# T01_Synth_Glove_v5.net
KiCad netlist of a schematic drawn in EAGLE
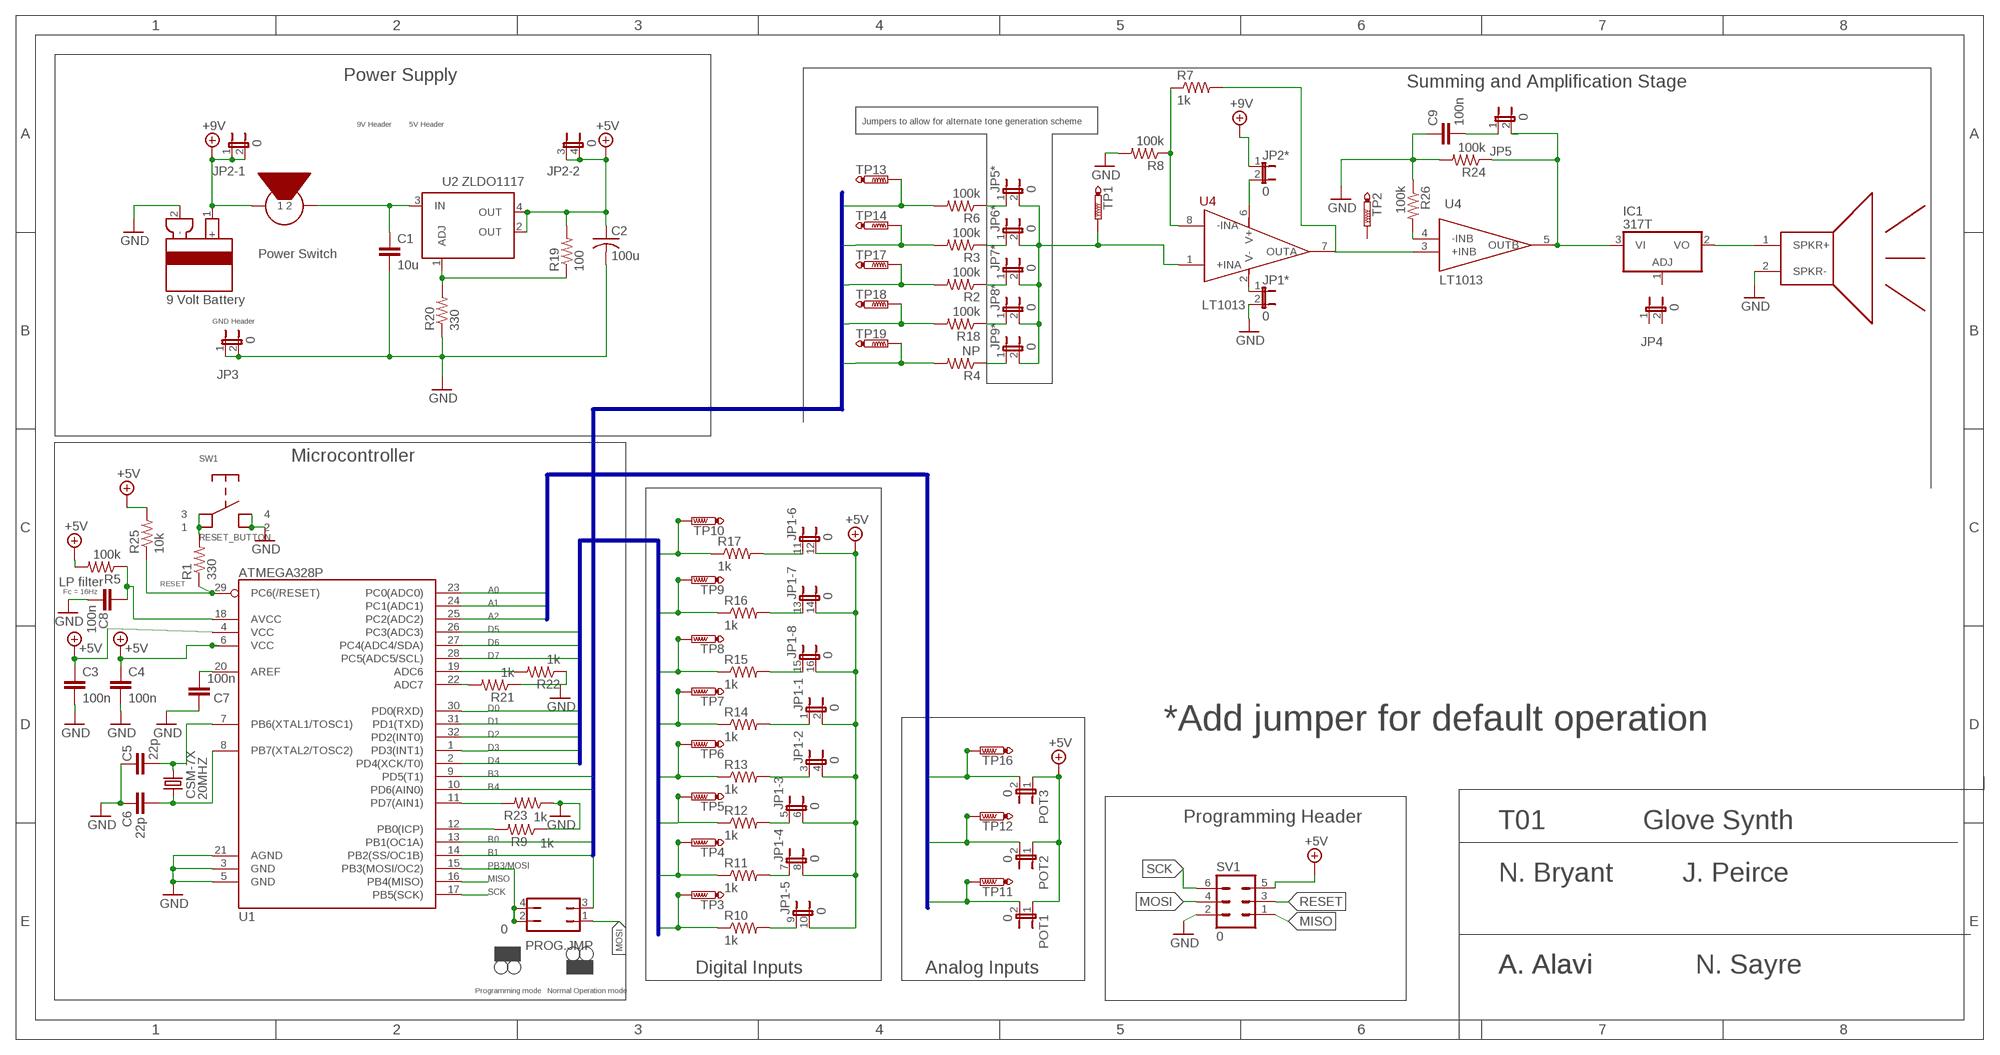
[diagram p0: schematic, sheet 1]

(export (version "E")
  (design (tool "Eeschema 10.0.6"))
  (components
    (comp (ref "20MHZ")
      (value "CSM-7X")
      (footprint "eagle-import:CSM-7X-DU")
      (libsource (lib "eagle-import") (part "CSM-7X-DU"))
    )
    (comp (ref "C1")
      (value "10u")
      (footprint "eagle-import:0603-CAP")
      (libsource (lib "eagle-import") (part "CAP0603-CAP"))
    )
    (comp (ref "C2")
      (value "100u")
      (footprint "eagle-import:C075-042X103")
      (libsource (lib "eagle-import") (part "C-US075-042X103"))
    )
    (comp (ref "C3")
      (value "100n")
      (footprint "eagle-import:0603-CAP")
      (libsource (lib "eagle-import") (part "CAP0603-CAP"))
    )
    (comp (ref "C4")
      (value "100n")
      (footprint "eagle-import:0603-CAP")
      (libsource (lib "eagle-import") (part "CAP0603-CAP"))
    )
    (comp (ref "C5")
      (value "22p")
      (footprint "eagle-import:0603-CAP")
      (libsource (lib "eagle-import") (part "CAP0603-CAP"))
    )
    (comp (ref "C6")
      (value "22p")
      (footprint "eagle-import:0603-CAP")
      (libsource (lib "eagle-import") (part "CAP0603-CAP"))
    )
    (comp (ref "C7")
      (value "100n")
      (footprint "eagle-import:0603-CAP")
      (libsource (lib "eagle-import") (part "CAP0603-CAP"))
    )
    (comp (ref "C8")
      (value "100n")
      (footprint "eagle-import:0603-CAP")
      (libsource (lib "eagle-import") (part "CAP0603-CAP"))
    )
    (comp (ref "C9")
      (value "100n")
      (footprint "eagle-import:0603-CAP")
      (libsource (lib "eagle-import") (part "CAP0603-CAP"))
    )
    (comp (ref "IC1")
      (value "317T")
      (footprint "eagle-import:TO220H")
      (libsource (lib "eagle-import") (part "317T"))
    )
    (comp (ref "JP1")
      (value "0")
      (footprint "eagle-import:JP8Q")
      (libsource (lib "eagle-import") (part "JP8QE"))
    )
    (comp (ref "JP1*")
      (value "0")
      (footprint "eagle-import:JP1")
      (libsource (lib "eagle-import") (part "JP1E"))
    )
    (comp (ref "JP2")
      (value "0")
      (footprint "eagle-import:JP2Q")
      (libsource (lib "eagle-import") (part "JP2QE"))
    )
    (comp (ref "JP2*")
      (value "0")
      (footprint "eagle-import:JP1")
      (libsource (lib "eagle-import") (part "JP1E"))
    )
    (comp (ref "JP3")
      (value "0")
      (footprint "eagle-import:JP1")
      (libsource (lib "eagle-import") (part "JP1E"))
    )
    (comp (ref "JP4")
      (value "0")
      (footprint "eagle-import:JP1")
      (libsource (lib "eagle-import") (part "JP1E"))
    )
    (comp (ref "JP5")
      (value "0")
      (footprint "eagle-import:JP1")
      (libsource (lib "eagle-import") (part "JP1E"))
    )
    (comp (ref "JP5*")
      (value "0")
      (footprint "eagle-import:JP1")
      (libsource (lib "eagle-import") (part "JP1E"))
    )
    (comp (ref "JP6*")
      (value "0")
      (footprint "eagle-import:JP1")
      (libsource (lib "eagle-import") (part "JP1E"))
    )
    (comp (ref "JP7*")
      (value "0")
      (footprint "eagle-import:JP1")
      (libsource (lib "eagle-import") (part "JP1E"))
    )
    (comp (ref "JP8*")
      (value "0")
      (footprint "eagle-import:JP1")
      (libsource (lib "eagle-import") (part "JP1E"))
    )
    (comp (ref "JP9*")
      (value "0")
      (footprint "eagle-import:JP1")
      (libsource (lib "eagle-import") (part "JP1E"))
    )
    (comp (ref "POT1")
      (value "0")
      (footprint "eagle-import:JP1")
      (libsource (lib "eagle-import") (part "JP1E"))
    )
    (comp (ref "POT2")
      (value "0")
      (footprint "eagle-import:JP1")
      (libsource (lib "eagle-import") (part "JP1E"))
    )
    (comp (ref "POT3")
      (value "0")
      (footprint "eagle-import:JP1")
      (libsource (lib "eagle-import") (part "JP1E"))
    )
    (comp (ref "PROG.JMP")
      (value "0")
      (footprint "eagle-import:JP2Q")
      (libsource (lib "eagle-import") (part "JP2Q"))
    )
    (comp (ref "R1")
      (value "330")
      (footprint "eagle-import:0603-RES")
      (libsource (lib "eagle-import") (part "RESISTOR0603"))
    )
    (comp (ref "R2")
      (value "100k")
      (footprint "eagle-import:0603-RES")
      (libsource (lib "eagle-import") (part "RESISTOR0603"))
    )
    (comp (ref "R3")
      (value "100k")
      (footprint "eagle-import:0603-RES")
      (libsource (lib "eagle-import") (part "RESISTOR0603"))
    )
    (comp (ref "R4")
      (value "NP")
      (footprint "eagle-import:0603-RES")
      (libsource (lib "eagle-import") (part "RESISTOR0603"))
    )
    (comp (ref "R5")
      (value "100k")
      (footprint "eagle-import:0603-RES")
      (libsource (lib "eagle-import") (part "RESISTOR0603"))
    )
    (comp (ref "R6")
      (value "100k")
      (footprint "eagle-import:0603-RES")
      (libsource (lib "eagle-import") (part "RESISTOR0603"))
    )
    (comp (ref "R7")
      (value "1k")
      (footprint "eagle-import:0603-RES")
      (libsource (lib "eagle-import") (part "RESISTOR0603"))
    )
    (comp (ref "R8")
      (value "100k")
      (footprint "eagle-import:0603-RES")
      (libsource (lib "eagle-import") (part "RESISTOR0603"))
    )
    (comp (ref "R9")
      (value "1k")
      (footprint "eagle-import:0603-RES")
      (libsource (lib "eagle-import") (part "RESISTOR0603"))
    )
    (comp (ref "R10")
      (value "1k")
      (footprint "eagle-import:0603-RES")
      (libsource (lib "eagle-import") (part "RESISTOR0603"))
    )
    (comp (ref "R11")
      (value "1k")
      (footprint "eagle-import:0603-RES")
      (libsource (lib "eagle-import") (part "RESISTOR0603"))
    )
    (comp (ref "R12")
      (value "1k")
      (footprint "eagle-import:0603-RES")
      (libsource (lib "eagle-import") (part "RESISTOR0603"))
    )
    (comp (ref "R13")
      (value "1k")
      (footprint "eagle-import:0603-RES")
      (libsource (lib "eagle-import") (part "RESISTOR0603"))
    )
    (comp (ref "R14")
      (value "1k")
      (footprint "eagle-import:0603-RES")
      (libsource (lib "eagle-import") (part "RESISTOR0603"))
    )
    (comp (ref "R15")
      (value "1k")
      (footprint "eagle-import:0603-RES")
      (libsource (lib "eagle-import") (part "RESISTOR0603"))
    )
    (comp (ref "R16")
      (value "1k")
      (footprint "eagle-import:0603-RES")
      (libsource (lib "eagle-import") (part "RESISTOR0603"))
    )
    (comp (ref "R17")
      (value "1k")
      (footprint "eagle-import:0603-RES")
      (libsource (lib "eagle-import") (part "RESISTOR0603"))
    )
    (comp (ref "R18")
      (value "100k")
      (footprint "eagle-import:0603-RES")
      (libsource (lib "eagle-import") (part "RESISTOR0603"))
    )
    (comp (ref "R19")
      (value "100")
      (footprint "eagle-import:0603-RES")
      (libsource (lib "eagle-import") (part "RESISTOR0603"))
    )
    (comp (ref "R20")
      (value "330")
      (footprint "eagle-import:0603-RES")
      (libsource (lib "eagle-import") (part "RESISTOR0603"))
    )
    (comp (ref "R21")
      (value "1k")
      (footprint "eagle-import:0603-RES")
      (libsource (lib "eagle-import") (part "RESISTOR0603"))
    )
    (comp (ref "R22")
      (value "1k")
      (footprint "eagle-import:0603-RES")
      (libsource (lib "eagle-import") (part "RESISTOR0603"))
    )
    (comp (ref "R23")
      (value "1k")
      (footprint "eagle-import:0603-RES")
      (libsource (lib "eagle-import") (part "RESISTOR0603"))
    )
    (comp (ref "R24")
      (value "100k")
      (footprint "eagle-import:0603-RES")
      (libsource (lib "eagle-import") (part "RESISTOR0603"))
    )
    (comp (ref "R25")
      (value "10k")
      (footprint "eagle-import:0603-RES")
      (libsource (lib "eagle-import") (part "RESISTOR0603"))
    )
    (comp (ref "R26")
      (value "100k")
      (footprint "eagle-import:0603-RES")
      (libsource (lib "eagle-import") (part "RESISTOR0603"))
    )
    (comp (ref "SV1")
      (value "0")
      (footprint "eagle-import:MA03-2")
      (libsource (lib "eagle-import") (part "MA03-2"))
    )
    (comp (ref "SW1")
      (value "RESET_BUTTON")
      (footprint "eagle-import:RESET_BUTTON")
      (libsource (lib "eagle-import") (part "RESET_BUTTON"))
    )
    (comp (ref "TP1")
      (value "PTR1B2,54")
      (footprint "eagle-import:B2,54")
      (libsource (lib "eagle-import") (part "PTR1B2,54"))
    )
    (comp (ref "TP2")
      (value "PTR1B2,54")
      (footprint "eagle-import:B2,54")
      (libsource (lib "eagle-import") (part "PTR1B2,54"))
    )
    (comp (ref "TP3")
      (value "PTR1B2,54")
      (footprint "eagle-import:B2,54")
      (libsource (lib "eagle-import") (part "PTR1B2,54"))
    )
    (comp (ref "TP4")
      (value "PTR1B2,54")
      (footprint "eagle-import:B2,54")
      (libsource (lib "eagle-import") (part "PTR1B2,54"))
    )
    (comp (ref "TP5")
      (value "PTR1B2,54")
      (footprint "eagle-import:B2,54")
      (libsource (lib "eagle-import") (part "PTR1B2,54"))
    )
    (comp (ref "TP6")
      (value "PTR1B2,54")
      (footprint "eagle-import:B2,54")
      (libsource (lib "eagle-import") (part "PTR1B2,54"))
    )
    (comp (ref "TP7")
      (value "PTR1B2,54")
      (footprint "eagle-import:B2,54")
      (libsource (lib "eagle-import") (part "PTR1B2,54"))
    )
    (comp (ref "TP8")
      (value "PTR1B2,54")
      (footprint "eagle-import:B2,54")
      (libsource (lib "eagle-import") (part "PTR1B2,54"))
    )
    (comp (ref "TP9")
      (value "PTR1B2,54")
      (footprint "eagle-import:B2,54")
      (libsource (lib "eagle-import") (part "PTR1B2,54"))
    )
    (comp (ref "TP10")
      (value "PTR1B2,54")
      (footprint "eagle-import:B2,54")
      (libsource (lib "eagle-import") (part "PTR1B2,54"))
    )
    (comp (ref "TP11")
      (value "PTR1B2,54")
      (footprint "eagle-import:B2,54")
      (libsource (lib "eagle-import") (part "PTR1B2,54"))
    )
    (comp (ref "TP12")
      (value "PTR1B2,54")
      (footprint "eagle-import:B2,54")
      (libsource (lib "eagle-import") (part "PTR1B2,54"))
    )
    (comp (ref "TP13")
      (value "PTR1B2,54")
      (footprint "eagle-import:B2,54")
      (libsource (lib "eagle-import") (part "PTR1B2,54"))
    )
    (comp (ref "TP14")
      (value "PTR1B2,54")
      (footprint "eagle-import:B2,54")
      (libsource (lib "eagle-import") (part "PTR1B2,54"))
    )
    (comp (ref "TP16")
      (value "PTR1B2,54")
      (footprint "eagle-import:B2,54")
      (libsource (lib "eagle-import") (part "PTR1B2,54"))
    )
    (comp (ref "TP17")
      (value "PTR1B2,54")
      (footprint "eagle-import:B2,54")
      (libsource (lib "eagle-import") (part "PTR1B2,54"))
    )
    (comp (ref "TP18")
      (value "PTR1B2,54")
      (footprint "eagle-import:B2,54")
      (libsource (lib "eagle-import") (part "PTR1B2,54"))
    )
    (comp (ref "TP19")
      (value "PTR1B2,54")
      (footprint "eagle-import:B2,54")
      (libsource (lib "eagle-import") (part "PTR1B2,54"))
    )
    (comp (ref "U$1")
      (value "SPEAKER")
      (footprint "eagle-import:JP1")
      (libsource (lib "eagle-import") (part "SPEAKER"))
    )
    (comp (ref "U$7")
      (value "POWER_SWITCH")
      (footprint "eagle-import:JP1")
      (libsource (lib "eagle-import") (part "POWER_SWITCH"))
    )
    (comp (ref "U$8")
      (value "9VOLTBATTERY")
      (footprint "eagle-import:JP1")
      (libsource (lib "eagle-import") (part "9VOLTBATTERY"))
    )
    (comp (ref "U1")
      (value "ATMEGA328P")
      (footprint "eagle-import:TQFP32-08")
      (libsource (lib "eagle-import") (part "ATMEGA328_SMT"))
    )
    (comp (ref "U2")
      (value "ZLDO1117")
      (footprint "eagle-import:SOT223")
      (libsource (lib "eagle-import") (part "ZLDO1117"))
    )
    (comp (ref "U4")
      (value "LT1013")
      (footprint "eagle-import:SO08")
      (libsource (lib "eagle-import") (part "LT1013"))
    )
  )
  (nets
    (net (code "1") (name "+5V") (class "Default")
      (node (ref "C2") (pin "1") (pinfunction "1_1") (pintype "passive"))
      (node (ref "C3") (pin "1") (pinfunction "1_1") (pintype "passive"))
      (node (ref "C4") (pin "1") (pinfunction "1_1") (pintype "passive"))
      (node (ref "JP1") (pin "10") (pinfunction "2_10") (pintype "passive"))
      (node (ref "JP1") (pin "12") (pinfunction "2_12") (pintype "passive"))
      (node (ref "JP1") (pin "14") (pinfunction "2_14") (pintype "passive"))
      (node (ref "JP1") (pin "16") (pinfunction "2_16") (pintype "passive"))
      (node (ref "JP1") (pin "2") (pinfunction "2_2") (pintype "passive"))
      (node (ref "JP1") (pin "4") (pinfunction "2_4") (pintype "passive"))
      (node (ref "JP1") (pin "6") (pinfunction "2_6") (pintype "passive"))
      (node (ref "JP1") (pin "8") (pinfunction "2_8") (pintype "passive"))
      (node (ref "JP2") (pin "3") (pinfunction "1_3") (pintype "passive"))
      (node (ref "JP2") (pin "4") (pinfunction "2_4") (pintype "passive"))
      (node (ref "POT1") (pin "1") (pinfunction "1_1") (pintype "passive"))
      (node (ref "POT2") (pin "1") (pinfunction "1_1") (pintype "passive"))
      (node (ref "POT3") (pin "1") (pinfunction "1_1") (pintype "passive"))
      (node (ref "R19") (pin "2") (pinfunction "2_2") (pintype "passive"))
      (node (ref "R25") (pin "2") (pinfunction "2_2") (pintype "passive"))
      (node (ref "R5") (pin "2") (pinfunction "2_2") (pintype "passive"))
      (node (ref "SV1") (pin "5") (pinfunction "5_5") (pintype "passive"))
      (node (ref "U1") (pin "4") (pinfunction "VCC_4") (pintype "bidirectional"))
      (node (ref "U1") (pin "6") (pinfunction "VCC_6") (pintype "bidirectional"))
      (node (ref "U2") (pin "2") (pinfunction "OUT_2") (pintype "bidirectional"))
      (node (ref "U2") (pin "4") (pinfunction "OUT_4") (pintype "bidirectional"))
    )
    (net (code "2") (name "+9V") (class "Default")
      (node (ref "JP2") (pin "1") (pinfunction "1_1") (pintype "passive"))
      (node (ref "JP2") (pin "2") (pinfunction "2_2") (pintype "passive"))
      (node (ref "JP2*") (pin "1") (pinfunction "1_1") (pintype "passive"))
      (node (ref "U$7") (pin "1") (pinfunction "1_1") (pintype "bidirectional"))
      (node (ref "U$8") (pin "1") (pinfunction "+_1") (pintype "bidirectional"))
    )
    (net (code "3") (name "/A0") (class "Default")
      (node (ref "POT1") (pin "2") (pinfunction "2_2") (pintype "passive"))
      (node (ref "TP11") (pin "TP") (pinfunction "TP_TP") (pintype "input"))
      (node (ref "U1") (pin "23") (pinfunction "PC0(ADC0)_23") (pintype "bidirectional"))
    )
    (net (code "4") (name "/A1") (class "Default")
      (node (ref "POT2") (pin "2") (pinfunction "2_2") (pintype "passive"))
      (node (ref "TP12") (pin "TP") (pinfunction "TP_TP") (pintype "input"))
      (node (ref "U1") (pin "24") (pinfunction "PC1(ADC1)_24") (pintype "bidirectional"))
    )
    (net (code "5") (name "/A2") (class "Default")
      (node (ref "POT3") (pin "2") (pinfunction "2_2") (pintype "passive"))
      (node (ref "TP16") (pin "TP") (pinfunction "TP_TP") (pintype "input"))
      (node (ref "U1") (pin "25") (pinfunction "PC2(ADC2)_25") (pintype "bidirectional"))
    )
    (net (code "6") (name "/B0") (class "Default")
      (node (ref "R6") (pin "2") (pinfunction "2_2") (pintype "passive"))
      (node (ref "TP13") (pin "TP") (pinfunction "TP_TP") (pintype "input"))
      (node (ref "U1") (pin "13") (pinfunction "PB1(OC1A)_13") (pintype "bidirectional"))
    )
    (net (code "7") (name "/B1") (class "Default")
      (node (ref "R2") (pin "2") (pinfunction "2_2") (pintype "passive"))
      (node (ref "R3") (pin "2") (pinfunction "2_2") (pintype "passive"))
      (node (ref "TP14") (pin "TP") (pinfunction "TP_TP") (pintype "input"))
      (node (ref "TP17") (pin "TP") (pinfunction "TP_TP") (pintype "input"))
      (node (ref "U1") (pin "14") (pinfunction "PB2(SS/OC1B)_14") (pintype "bidirectional"))
    )
    (net (code "8") (name "/B3") (class "Default")
      (node (ref "R18") (pin "2") (pinfunction "2_2") (pintype "passive"))
      (node (ref "TP18") (pin "TP") (pinfunction "TP_TP") (pintype "input"))
      (node (ref "U1") (pin "9") (pinfunction "PD5(T1)_9") (pintype "bidirectional"))
    )
    (net (code "9") (name "/B4") (class "Default")
      (node (ref "R4") (pin "2") (pinfunction "2_2") (pintype "passive"))
      (node (ref "TP19") (pin "TP") (pinfunction "TP_TP") (pintype "input"))
      (node (ref "U1") (pin "10") (pinfunction "PD6(AIN0)_10") (pintype "bidirectional"))
    )
    (net (code "10") (name "/D0") (class "Default")
      (node (ref "R10") (pin "1") (pinfunction "1_1") (pintype "passive"))
      (node (ref "TP3") (pin "TP") (pinfunction "TP_TP") (pintype "input"))
      (node (ref "U1") (pin "30") (pinfunction "PD0(RXD)_30") (pintype "bidirectional"))
    )
    (net (code "11") (name "/D1") (class "Default")
      (node (ref "R11") (pin "1") (pinfunction "1_1") (pintype "passive"))
      (node (ref "TP4") (pin "TP") (pinfunction "TP_TP") (pintype "input"))
      (node (ref "U1") (pin "31") (pinfunction "PD1(TXD)_31") (pintype "bidirectional"))
    )
    (net (code "12") (name "/D2") (class "Default")
      (node (ref "R12") (pin "1") (pinfunction "1_1") (pintype "passive"))
      (node (ref "TP5") (pin "TP") (pinfunction "TP_TP") (pintype "input"))
      (node (ref "U1") (pin "32") (pinfunction "PD2(INT0)_32") (pintype "bidirectional"))
    )
    (net (code "13") (name "/D3") (class "Default")
      (node (ref "R13") (pin "1") (pinfunction "1_1") (pintype "passive"))
      (node (ref "TP6") (pin "TP") (pinfunction "TP_TP") (pintype "input"))
      (node (ref "U1") (pin "1") (pinfunction "PD3(INT1)_1") (pintype "bidirectional"))
    )
    (net (code "14") (name "/D4") (class "Default")
      (node (ref "R14") (pin "1") (pinfunction "1_1") (pintype "passive"))
      (node (ref "TP7") (pin "TP") (pinfunction "TP_TP") (pintype "input"))
      (node (ref "U1") (pin "2") (pinfunction "PD4(XCK/T0)_2") (pintype "bidirectional"))
    )
    (net (code "15") (name "/D5") (class "Default")
      (node (ref "R15") (pin "1") (pinfunction "1_1") (pintype "passive"))
      (node (ref "TP8") (pin "TP") (pinfunction "TP_TP") (pintype "input"))
      (node (ref "U1") (pin "26") (pinfunction "PC3(ADC3)_26") (pintype "bidirectional"))
    )
    (net (code "16") (name "/D6") (class "Default")
      (node (ref "R16") (pin "1") (pinfunction "1_1") (pintype "passive"))
      (node (ref "TP9") (pin "TP") (pinfunction "TP_TP") (pintype "input"))
      (node (ref "U1") (pin "27") (pinfunction "PC4(ADC4/SDA)_27") (pintype "bidirectional"))
    )
    (net (code "17") (name "/D7") (class "Default")
      (node (ref "R17") (pin "1") (pinfunction "1_1") (pintype "passive"))
      (node (ref "TP10") (pin "TP") (pinfunction "TP_TP") (pintype "input"))
      (node (ref "U1") (pin "28") (pinfunction "PC5(ADC5/SCL)_28") (pintype "bidirectional"))
    )
    (net (code "18") (name "/PB3{slash}MOSI") (class "Default")
      (node (ref "PROG.JMP") (pin "2") (pinfunction "2_2") (pintype "passive"))
      (node (ref "PROG.JMP") (pin "4") (pinfunction "4_4") (pintype "passive"))
      (node (ref "U1") (pin "15") (pinfunction "PB3(MOSI/OC2)_15") (pintype "bidirectional"))
    )
    (net (code "19") (name "GND") (class "Default")
      (node (ref "C1") (pin "2") (pinfunction "2_2") (pintype "passive"))
      (node (ref "C2") (pin "2") (pinfunction "2_2") (pintype "passive"))
      (node (ref "C3") (pin "2") (pinfunction "2_2") (pintype "passive"))
      (node (ref "C4") (pin "2") (pinfunction "2_2") (pintype "passive"))
      (node (ref "C5") (pin "2") (pinfunction "2_2") (pintype "passive"))
      (node (ref "C6") (pin "2") (pinfunction "2_2") (pintype "passive"))
      (node (ref "C7") (pin "2") (pinfunction "2_2") (pintype "passive"))
      (node (ref "C8") (pin "2") (pinfunction "2_2") (pintype "passive"))
      (node (ref "C9") (pin "1") (pinfunction "1_1") (pintype "passive"))
      (node (ref "JP1*") (pin "2") (pinfunction "2_2") (pintype "passive"))
      (node (ref "JP3") (pin "1") (pinfunction "1_1") (pintype "passive"))
      (node (ref "JP3") (pin "2") (pinfunction "2_2") (pintype "passive"))
      (node (ref "R20") (pin "1") (pinfunction "1_1") (pintype "passive"))
      (node (ref "R21") (pin "1") (pinfunction "1_1") (pintype "passive"))
      (node (ref "R22") (pin "1") (pinfunction "1_1") (pintype "passive"))
      (node (ref "R23") (pin "1") (pinfunction "1_1") (pintype "passive"))
      (node (ref "R24") (pin "2") (pinfunction "2_2") (pintype "passive"))
      (node (ref "R26") (pin "1") (pinfunction "1_1") (pintype "passive"))
      (node (ref "R8") (pin "2") (pinfunction "2_2") (pintype "passive"))
      (node (ref "R9") (pin "1") (pinfunction "1_1") (pintype "passive"))
      (node (ref "SV1") (pin "2") (pinfunction "2_2") (pintype "passive"))
      (node (ref "SW1") (pin "2") (pinfunction "2_2") (pintype "bidirectional"))
      (node (ref "SW1") (pin "4") (pinfunction "4_4") (pintype "bidirectional"))
      (node (ref "U$1") (pin "2") (pinfunction "SPKR-_2") (pintype "bidirectional"))
      (node (ref "U$8") (pin "2") (pinfunction "-_2") (pintype "bidirectional"))
      (node (ref "U1") (pin "21") (pinfunction "AGND_21") (pintype "bidirectional"))
      (node (ref "U1") (pin "3") (pinfunction "GND_3") (pintype "bidirectional"))
      (node (ref "U1") (pin "5") (pinfunction "GND_5") (pintype "bidirectional"))
    )
    (net (code "20") (name "MISO") (class "Default")
      (node (ref "SV1") (pin "1") (pinfunction "1_1") (pintype "passive"))
      (node (ref "U1") (pin "16") (pinfunction "PB4(MISO)_16") (pintype "bidirectional"))
    )
    (net (code "21") (name "MOSI") (class "Default")
      (node (ref "PROG.JMP") (pin "1") (pinfunction "1_1") (pintype "passive"))
      (node (ref "SV1") (pin "4") (pinfunction "4_4") (pintype "passive"))
    )
    (net (code "22") (name "Net-(C9-Pad2)") (class "Default")
      (node (ref "C9") (pin "2") (pinfunction "2_2") (pintype "passive"))
      (node (ref "JP5") (pin "1") (pinfunction "1_1") (pintype "passive"))
    )
    (net (code "23") (name "Net-(IC1-VI)") (class "Default")
      (node (ref "IC1") (pin "3") (pinfunction "VI_3") (pintype "input"))
      (node (ref "JP5") (pin "2") (pinfunction "2_2") (pintype "passive"))
      (node (ref "R24") (pin "1") (pinfunction "1_1") (pintype "passive"))
      (node (ref "U4") (pin "5") (pinfunction "OUTB_5") (pintype "bidirectional"))
    )
    (net (code "24") (name "Net-(IC1-VO)") (class "Default")
      (node (ref "IC1") (pin "2") (pinfunction "VO_2") (pintype "passive"))
      (node (ref "U$1") (pin "1") (pinfunction "SPKR+_1") (pintype "bidirectional"))
    )
    (net (code "25") (name "Net-(JP1-Pad1)") (class "Default")
      (node (ref "JP1") (pin "1") (pinfunction "1_1") (pintype "passive"))
      (node (ref "R14") (pin "2") (pinfunction "2_2") (pintype "passive"))
    )
    (net (code "26") (name "Net-(JP1B-1)") (class "Default")
      (node (ref "JP1") (pin "3") (pinfunction "1_3") (pintype "passive"))
      (node (ref "R13") (pin "2") (pinfunction "2_2") (pintype "passive"))
    )
    (net (code "27") (name "Net-(JP1C-1)") (class "Default")
      (node (ref "JP1") (pin "5") (pinfunction "1_5") (pintype "passive"))
      (node (ref "R12") (pin "2") (pinfunction "2_2") (pintype "passive"))
    )
    (net (code "28") (name "Net-(JP1D-1)") (class "Default")
      (node (ref "JP1") (pin "7") (pinfunction "1_7") (pintype "passive"))
      (node (ref "R11") (pin "2") (pinfunction "2_2") (pintype "passive"))
    )
    (net (code "29") (name "Net-(JP1E-1)") (class "Default")
      (node (ref "JP1") (pin "9") (pinfunction "1_9") (pintype "passive"))
      (node (ref "R10") (pin "2") (pinfunction "2_2") (pintype "passive"))
    )
    (net (code "30") (name "Net-(JP1F-1)") (class "Default")
      (node (ref "JP1") (pin "11") (pinfunction "1_11") (pintype "passive"))
      (node (ref "R17") (pin "2") (pinfunction "2_2") (pintype "passive"))
    )
    (net (code "31") (name "Net-(JP1G-1)") (class "Default")
      (node (ref "JP1") (pin "13") (pinfunction "1_13") (pintype "passive"))
      (node (ref "R16") (pin "2") (pinfunction "2_2") (pintype "passive"))
    )
    (net (code "32") (name "Net-(JP1H-1)") (class "Default")
      (node (ref "JP1") (pin "15") (pinfunction "1_15") (pintype "passive"))
      (node (ref "R15") (pin "2") (pinfunction "2_2") (pintype "passive"))
    )
    (net (code "33") (name "Net-(JP5*-Pad1)") (class "Default")
      (node (ref "JP5*") (pin "1") (pinfunction "1_1") (pintype "passive"))
      (node (ref "R6") (pin "1") (pinfunction "1_1") (pintype "passive"))
    )
    (net (code "34") (name "Net-(JP6*-Pad1)") (class "Default")
      (node (ref "JP6*") (pin "1") (pinfunction "1_1") (pintype "passive"))
      (node (ref "R3") (pin "1") (pinfunction "1_1") (pintype "passive"))
    )
    (net (code "35") (name "Net-(JP7*-Pad1)") (class "Default")
      (node (ref "JP7*") (pin "1") (pinfunction "1_1") (pintype "passive"))
      (node (ref "R2") (pin "1") (pinfunction "1_1") (pintype "passive"))
    )
    (net (code "36") (name "Net-(JP8*-Pad1)") (class "Default")
      (node (ref "JP8*") (pin "1") (pinfunction "1_1") (pintype "passive"))
      (node (ref "R18") (pin "1") (pinfunction "1_1") (pintype "passive"))
    )
    (net (code "37") (name "Net-(JP9*-Pad1)") (class "Default")
      (node (ref "JP9*") (pin "1") (pinfunction "1_1") (pintype "passive"))
      (node (ref "R4") (pin "1") (pinfunction "1_1") (pintype "passive"))
    )
    (net (code "38") (name "Net-(R1-Pad2)") (class "Default")
      (node (ref "R1") (pin "2") (pinfunction "2_2") (pintype "passive"))
      (node (ref "SW1") (pin "1") (pinfunction "1_1") (pintype "bidirectional"))
      (node (ref "SW1") (pin "3") (pinfunction "3_3") (pintype "bidirectional"))
    )
    (net (code "39") (name "Net-(U1-ADC6)") (class "Default")
      (node (ref "R22") (pin "2") (pinfunction "2_2") (pintype "passive"))
      (node (ref "U1") (pin "19") (pinfunction "ADC6_19") (pintype "bidirectional"))
    )
    (net (code "40") (name "Net-(U1-ADC7)") (class "Default")
      (node (ref "R21") (pin "2") (pinfunction "2_2") (pintype "passive"))
      (node (ref "U1") (pin "22") (pinfunction "ADC7_22") (pintype "bidirectional"))
    )
    (net (code "41") (name "Net-(U1-AREF)") (class "Default")
      (node (ref "C7") (pin "1") (pinfunction "1_1") (pintype "passive"))
      (node (ref "U1") (pin "20") (pinfunction "AREF_20") (pintype "bidirectional"))
    )
    (net (code "42") (name "Net-(U1-AVCC)") (class "Default")
      (node (ref "C8") (pin "1") (pinfunction "1_1") (pintype "passive"))
      (node (ref "R5") (pin "1") (pinfunction "1_1") (pintype "passive"))
      (node (ref "U1") (pin "18") (pinfunction "AVCC_18") (pintype "bidirectional"))
    )
    (net (code "43") (name "Net-(U1-PB0(ICP))") (class "Default")
      (node (ref "R9") (pin "2") (pinfunction "2_2") (pintype "passive"))
      (node (ref "U1") (pin "12") (pinfunction "PB0(ICP)_12") (pintype "bidirectional"))
    )
    (net (code "44") (name "Net-(U1-PB6(XTAL1{slash}TOSC1))") (class "Default")
      (node (ref "20MHZ") (pin "1") (pinfunction "1_1") (pintype "passive"))
      (node (ref "C5") (pin "1") (pinfunction "1_1") (pintype "passive"))
      (node (ref "U1") (pin "7") (pinfunction "PB6(XTAL1/TOSC1)_7") (pintype "bidirectional"))
    )
    (net (code "45") (name "Net-(U1-PB7(XTAL2{slash}TOSC2))") (class "Default")
      (node (ref "20MHZ") (pin "2") (pinfunction "2_2") (pintype "passive"))
      (node (ref "C6") (pin "1") (pinfunction "1_1") (pintype "passive"))
      (node (ref "U1") (pin "8") (pinfunction "PB7(XTAL2/TOSC2)_8") (pintype "bidirectional"))
    )
    (net (code "46") (name "Net-(U1-PD7(AIN1))") (class "Default")
      (node (ref "R23") (pin "2") (pinfunction "2_2") (pintype "passive"))
      (node (ref "U1") (pin "11") (pinfunction "PD7(AIN1)_11") (pintype "bidirectional"))
    )
    (net (code "47") (name "Net-(U2-ADJ)") (class "Default")
      (node (ref "R19") (pin "1") (pinfunction "1_1") (pintype "passive"))
      (node (ref "R20") (pin "2") (pinfunction "2_2") (pintype "passive"))
      (node (ref "U2") (pin "1") (pinfunction "ADJ_1") (pintype "bidirectional"))
    )
    (net (code "48") (name "Net-(U2-IN)") (class "Default")
      (node (ref "C1") (pin "1") (pinfunction "1_1") (pintype "passive"))
      (node (ref "U$7") (pin "2") (pinfunction "2_2") (pintype "bidirectional"))
      (node (ref "U2") (pin "3") (pinfunction "IN_3") (pintype "bidirectional"))
    )
    (net (code "49") (name "Net-(U4-+INA)") (class "Default")
      (node (ref "JP5*") (pin "2") (pinfunction "2_2") (pintype "passive"))
      (node (ref "JP6*") (pin "2") (pinfunction "2_2") (pintype "passive"))
      (node (ref "JP7*") (pin "2") (pinfunction "2_2") (pintype "passive"))
      (node (ref "JP8*") (pin "2") (pinfunction "2_2") (pintype "passive"))
      (node (ref "JP9*") (pin "2") (pinfunction "2_2") (pintype "passive"))
      (node (ref "TP1") (pin "TP") (pinfunction "TP_TP") (pintype "input"))
      (node (ref "U4") (pin "1") (pinfunction "+INA_1") (pintype "bidirectional"))
    )
    (net (code "50") (name "Net-(U4--INA)") (class "Default")
      (node (ref "R7") (pin "1") (pinfunction "1_1") (pintype "passive"))
      (node (ref "R8") (pin "1") (pinfunction "1_1") (pintype "passive"))
      (node (ref "U4") (pin "8") (pinfunction "-INA_8") (pintype "bidirectional"))
    )
    (net (code "51") (name "Net-(U4--INB)") (class "Default")
      (node (ref "R26") (pin "2") (pinfunction "2_2") (pintype "passive"))
      (node (ref "U4") (pin "4") (pinfunction "-INB_4") (pintype "bidirectional"))
    )
    (net (code "52") (name "Net-(U4-OUTA)") (class "Default")
      (node (ref "R7") (pin "2") (pinfunction "2_2") (pintype "passive"))
      (node (ref "U4") (pin "7") (pinfunction "OUTA_7") (pintype "bidirectional"))
    )
    (net (code "53") (name "Net-(U4-V+)") (class "Default")
      (node (ref "JP2*") (pin "2") (pinfunction "2_2") (pintype "passive"))
      (node (ref "U4") (pin "6") (pinfunction "V+_6") (pintype "power_in"))
    )
    (net (code "54") (name "Net-(U4-V-)") (class "Default")
      (node (ref "JP1*") (pin "1") (pinfunction "1_1") (pintype "passive"))
      (node (ref "U4") (pin "2") (pinfunction "V-_2") (pintype "power_in"))
    )
    (net (code "55") (name "RESET") (class "Default")
      (node (ref "R1") (pin "1") (pinfunction "1_1") (pintype "passive"))
      (node (ref "R25") (pin "1") (pinfunction "1_1") (pintype "passive"))
      (node (ref "SV1") (pin "3") (pinfunction "3_3") (pintype "passive"))
      (node (ref "U1") (pin "29") (pinfunction "PC6(/RESET)_29") (pintype "bidirectional"))
    )
    (net (code "56") (name "SCK") (class "Default")
      (node (ref "SV1") (pin "6") (pinfunction "6_6") (pintype "passive"))
      (node (ref "U1") (pin "17") (pinfunction "PB5(SCK)_17") (pintype "bidirectional"))
    )
    (net (code "57") (name "unconnected-(IC1-ADJ-Pad1)") (class "Default")
      (node (ref "IC1") (pin "1") (pinfunction "ADJ_1") (pintype "input"))
    )
    (net (code "58") (name "unconnected-(JP4-Pad1)") (class "Default")
      (node (ref "JP4") (pin "1") (pinfunction "1_1") (pintype "passive"))
    )
    (net (code "59") (name "unconnected-(JP4-Pad2)") (class "Default")
      (node (ref "JP4") (pin "2") (pinfunction "2_2") (pintype "passive"))
    )
    (net (code "60") (name "unconnected-(PROG.JMP-Pad3)") (class "Default")
      (node (ref "PROG.JMP") (pin "3") (pinfunction "3_3") (pintype "passive"))
    )
    (net (code "61") (name "unconnected-(TP2-PadTP)") (class "Default")
      (node (ref "TP2") (pin "TP") (pinfunction "TP_TP") (pintype "input"))
    )
    (net (code "62") (name "unconnected-(U4-+INB-Pad3)") (class "Default")
      (node (ref "U4") (pin "3") (pinfunction "+INB_3") (pintype "bidirectional"))
    )
  )
)
